# P3V3_Regulator.net
KiCad netlist of a schematic drawn in Altium Designer
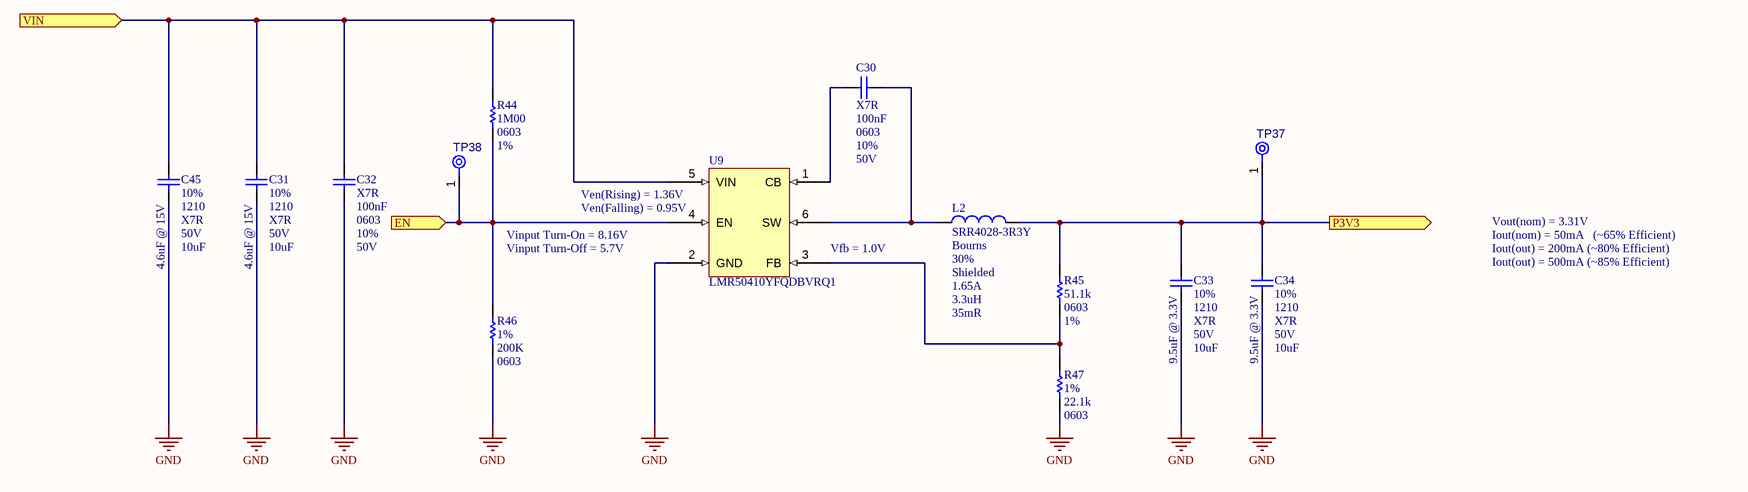
[diagram p0: P3V3_Regulator.SchDoc]

(export (version "E")
  (design (tool "Eeschema 10.0.6"))
  (components
    (comp (ref "C30")
      (value "100nF")
      (footprint "CAPC1608X90X40ML10T20")
      (description "Chip Capacitor, 100nF, +/- 10%, 50 V, X7R 0603 (1608 Metric)")
      (fields
        (field (name "DIELECTRIC") "X7R")
        (field (name "CASE/PACKAGE") "0603")
        (field (name "TOLERANCE") "10%")
        (field (name "VOLTAGE RATING") "50V")
        (field (name "Comment") "Capacitor 100nF +/- 10%, 50V, X7R, 0603")
      )
      (libsource (lib "Applied Physics Lab") (part "CAP-NP-2"))
    )
    (comp (ref "C31")
      (value "10uF")
      (footprint "CAPC3225X270X30ML30")
      (description "Chip Capacitor, 10uF, 10%, 50 V, X7R 1210 (3225 Metric)")
      (fields
        (field (name "TOLERANCE") "10%")
        (field (name "CASE/PACKAGE") "1210")
        (field (name "DIELECTRIC") "X7R")
        (field (name "VOLTAGE RATING") "50V")
        (field (name "Comment") "Capacitor 10uF 10%, 50V, X7R, 1210")
      )
      (libsource (lib "Applied Physics Lab") (part "CAP-NP-2"))
    )
    (comp (ref "C32")
      (value "100nF")
      (footprint "CAPC1608X90X40ML10T20")
      (description "Chip Capacitor, 100nF, +/- 10%, 50 V, X7R 0603 (1608 Metric)")
      (fields
        (field (name "DIELECTRIC") "X7R")
        (field (name "CASE/PACKAGE") "0603")
        (field (name "TOLERANCE") "10%")
        (field (name "VOLTAGE RATING") "50V")
        (field (name "Comment") "Capacitor 100nF +/- 10%, 50V, X7R, 0603")
      )
      (libsource (lib "Applied Physics Lab") (part "CAP-NP-2"))
    )
    (comp (ref "C33")
      (value "10uF")
      (footprint "CAPC3225X270X30ML30")
      (description "Chip Capacitor, 10uF, 10%, 50 V, X7R 1210 (3225 Metric)")
      (fields
        (field (name "TOLERANCE") "10%")
        (field (name "CASE/PACKAGE") "1210")
        (field (name "DIELECTRIC") "X7R")
        (field (name "VOLTAGE RATING") "50V")
        (field (name "Comment") "Capacitor 10uF 10%, 50V, X7R, 1210")
      )
      (libsource (lib "Applied Physics Lab") (part "CAP-NP-2"))
    )
    (comp (ref "C34")
      (value "10uF")
      (footprint "CAPC3225X270X30ML30")
      (description "Chip Capacitor, 10uF, 10%, 50 V, X7R 1210 (3225 Metric)")
      (fields
        (field (name "TOLERANCE") "10%")
        (field (name "CASE/PACKAGE") "1210")
        (field (name "DIELECTRIC") "X7R")
        (field (name "VOLTAGE RATING") "50V")
        (field (name "Comment") "Capacitor 10uF 10%, 50V, X7R, 1210")
      )
      (libsource (lib "Applied Physics Lab") (part "CAP-NP-2"))
    )
    (comp (ref "C45")
      (value "10uF")
      (footprint "CAPC3225X270X30ML30")
      (description "Chip Capacitor, 10uF, 10%, 50 V, X7R 1210 (3225 Metric)")
      (fields
        (field (name "TOLERANCE") "10%")
        (field (name "CASE/PACKAGE") "1210")
        (field (name "DIELECTRIC") "X7R")
        (field (name "VOLTAGE RATING") "50V")
        (field (name "Comment") "Capacitor 10uF 10%, 50V, X7R, 1210")
      )
      (libsource (lib "Applied Physics Lab") (part "CAP-NP-2"))
    )
    (comp (ref "L2")
      (value "SRR4028-3R3Y")
      (footprint "INDP4848X30M")
      (description "Inductor Power Shielded Wirewound 3.3uH 30% 7.72 Q-Factor Ferrite 1.65A Saturation 35mROhm DCR")
      (fields
        (field (name "MANUFACTURER") "Bourns")
        (field (name "INDUCTANCE TOLERANCE") "30%")
        (field (name "SHIELDING") "Shielded")
        (field (name "SATURATION CURRENT") "1.65A")
        (field (name "INDUCTANCE") "3.3uH")
        (field (name "DC RESISTANCE (DCR)") "35mR")
      )
      (libsource (lib "Applied Physics Lab") (part "IND-2"))
    )
    (comp (ref "R44")
      (value "1M00")
      (footprint "RESC1609X50X30ML08T20")
      (description "Chip Resistor, 1M Ohm, +/- 1%, 0.1 W, -55 to 155 degC, 0603 (1608 Metric)")
      (fields
        (field (name "POWER") "100mW")
        (field (name "CASE/PACKAGE") "0603")
        (field (name "TOLERANCE") "1%")
        (field (name "Comment") "Resistor 1M +/-1% 0603 100 mW")
      )
      (libsource (lib "Applied Physics Lab") (part "RES-2"))
    )
    (comp (ref "R45")
      (value "51.1k")
      (footprint "RESC1608X55X25ML10T15")
      (description "Chip Resistor, 51.1k Ohm, +/- 1%, 0.1 W, -55 to 155 degC, 0603 (1608 Metric)")
      (fields
        (field (name "CASE/PACKAGE") "0603")
        (field (name "POWER") "100mW")
        (field (name "TOLERANCE") "1%")
        (field (name "Comment") "Resistor 51K1 +/-1% 0603 100 mW")
      )
      (libsource (lib "Applied Physics Lab") (part "RES-2"))
    )
    (comp (ref "R46")
      (value "200K")
      (footprint "RESC1609X50X30ML08T20")
      (description "Chip Resistor, 200k Ohm, +/- 1%, 0.1 W, -55 to 155 degC, 0603 (1608 Metric)")
      (fields
        (field (name "POWER") "100mW")
        (field (name "TOLERANCE") "1%")
        (field (name "CASE/PACKAGE") "0603")
        (field (name "Comment") "Resistor 200K +/-1% 0603 100 mW")
      )
      (libsource (lib "Applied Physics Lab") (part "RES-2"))
    )
    (comp (ref "R47")
      (value "22.1k")
      (footprint "RESC1608X55X25ML10T15")
      (description "Chip Resistor, 22.1k Ohm, +/- 1%, 0.1 W, -55 to 155 degC, 0603 (1608 Metric)")
      (fields
        (field (name "TOLERANCE") "1%")
        (field (name "POWER") "100mW")
        (field (name "CASE/PACKAGE") "0603")
        (field (name "Comment") "Resistor 22K1 +/-1% 0603 100 mW")
      )
      (libsource (lib "Applied Physics Lab") (part "RES-2"))
    )
    (comp (ref "TP37")
      (value "TPAD6R-CIRCLED")
      (footprint "TP06R - Circled")
      (description "0.6mm round with a silkscreen circle.")
      (libsource (lib "Applied Physics Lab") (part "CMP-001-0001-4"))
    )
    (comp (ref "TP38")
      (value "TPAD6R-CIRCLED")
      (footprint "TP06R - Circled")
      (description "0.6mm round with a silkscreen circle.")
      (libsource (lib "Applied Physics Lab") (part "CMP-001-0001-4"))
    )
    (comp (ref "U9")
      (value "LMR50410YFQDBVRQ1")
      (footprint "SOT95P280X145-6M")
      (libsource (lib "Applied Physics Lab") (part "LMR50410YFQDBVRQ1-Symbol-1"))
    )
  )
  (nets
    (net (code "1") (name "/EN") (class "Default")
      (node (ref "R44") (pin "1") (pinfunction "1_1") (pintype "passive"))
      (node (ref "R46") (pin "2") (pinfunction "2_2") (pintype "passive"))
      (node (ref "TP38") (pin "1") (pinfunction "TP_1") (pintype "passive"))
      (node (ref "U9") (pin "4") (pinfunction "EN_4") (pintype "input"))
    )
    (net (code "2") (name "/P3V3") (class "Default")
      (node (ref "C33") (pin "2") (pinfunction "2_2") (pintype "passive"))
      (node (ref "C34") (pin "2") (pinfunction "2_2") (pintype "passive"))
      (node (ref "L2") (pin "2") (pinfunction "2_2") (pintype "passive"))
      (node (ref "R45") (pin "1") (pinfunction "1_1") (pintype "passive"))
      (node (ref "TP37") (pin "1") (pinfunction "TP_1") (pintype "passive"))
    )
    (net (code "3") (name "/VIN") (class "Default")
      (node (ref "C31") (pin "2") (pinfunction "2_2") (pintype "passive"))
      (node (ref "C32") (pin "2") (pinfunction "2_2") (pintype "passive"))
      (node (ref "C45") (pin "2") (pinfunction "2_2") (pintype "passive"))
      (node (ref "R44") (pin "2") (pinfunction "2_2") (pintype "passive"))
      (node (ref "U9") (pin "5") (pinfunction "VIN_5") (pintype "input"))
    )
    (net (code "4") (name "GND") (class "Default")
      (node (ref "C31") (pin "1") (pinfunction "1_1") (pintype "passive"))
      (node (ref "C32") (pin "1") (pinfunction "1_1") (pintype "passive"))
      (node (ref "C33") (pin "1") (pinfunction "1_1") (pintype "passive"))
      (node (ref "C34") (pin "1") (pinfunction "1_1") (pintype "passive"))
      (node (ref "C45") (pin "1") (pinfunction "1_1") (pintype "passive"))
      (node (ref "R46") (pin "1") (pinfunction "1_1") (pintype "passive"))
      (node (ref "R47") (pin "1") (pinfunction "1_1") (pintype "passive"))
      (node (ref "U9") (pin "2") (pinfunction "GND_2") (pintype "input"))
    )
    (net (code "5") (name "Net-(U9-CB)") (class "Default")
      (node (ref "C30") (pin "2") (pinfunction "2_2") (pintype "passive"))
      (node (ref "U9") (pin "1") (pinfunction "CB_1") (pintype "input"))
    )
    (net (code "6") (name "Net-(U9-FB)") (class "Default")
      (node (ref "R45") (pin "2") (pinfunction "2_2") (pintype "passive"))
      (node (ref "R47") (pin "2") (pinfunction "2_2") (pintype "passive"))
      (node (ref "U9") (pin "3") (pinfunction "FB_3") (pintype "input"))
    )
    (net (code "7") (name "Net-(U9-SW)") (class "Default")
      (node (ref "C30") (pin "1") (pinfunction "1_1") (pintype "passive"))
      (node (ref "L2") (pin "1") (pinfunction "1_1") (pintype "passive"))
      (node (ref "U9") (pin "6") (pinfunction "SW_6") (pintype "input"))
    )
  )
)
